# top.net
KiCad netlist of a schematic drawn in Altium Designer
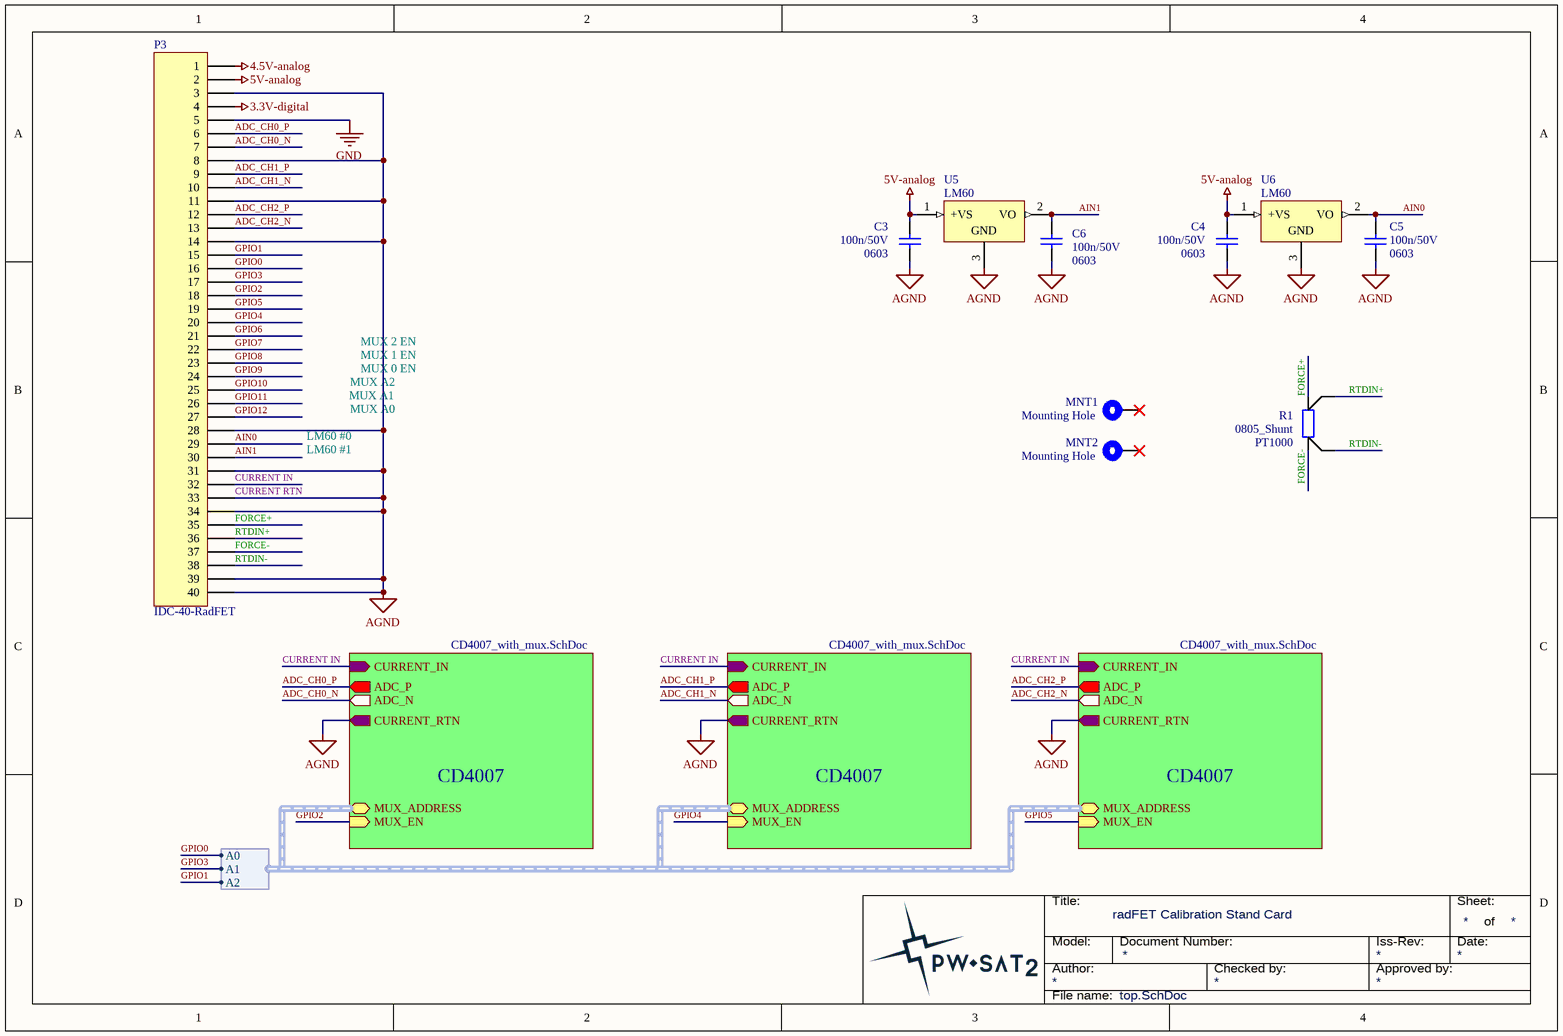
[diagram p0: top.SchDoc]

(export (version "E")
  (design (tool "Eeschema 10.0.6"))
  (components
    (comp (ref "C3")
      (value "100n/50V")
      (footprint "SMD_Capacitor_0603")
      (description "Ceramic Cap Kemet COTS 100n/50V X7R 0603")
      (fields
        (field (name "MANUFACTURER") "Kemet")
        (field (name "MANUFACTURERPARTNUMBER") "C0603T104K5RALTU")
        (field (name "PACKAGE") "0603")
      )
      (libsource (lib "capacitors") (part "Cer_C0603T104K5RALTU"))
    )
    (comp (ref "C4")
      (value "100n/50V")
      (footprint "SMD_Capacitor_0603")
      (description "Ceramic Cap Kemet COTS 100n/50V X7R 0603")
      (fields
        (field (name "MANUFACTURER") "Kemet")
        (field (name "MANUFACTURERPARTNUMBER") "C0603T104K5RALTU")
        (field (name "PACKAGE") "0603")
      )
      (libsource (lib "capacitors") (part "Cer_C0603T104K5RALTU"))
    )
    (comp (ref "C5")
      (value "100n/50V")
      (footprint "SMD_Capacitor_0603")
      (description "Ceramic Cap Kemet COTS 100n/50V X7R 0603")
      (fields
        (field (name "MANUFACTURER") "Kemet")
        (field (name "MANUFACTURERPARTNUMBER") "C0603T104K5RALTU")
        (field (name "PACKAGE") "0603")
      )
      (libsource (lib "capacitors") (part "Cer_C0603T104K5RALTU"))
    )
    (comp (ref "C6")
      (value "100n/50V")
      (footprint "SMD_Capacitor_0603")
      (description "Ceramic Cap Kemet COTS 100n/50V X7R 0603")
      (fields
        (field (name "MANUFACTURER") "Kemet")
        (field (name "MANUFACTURERPARTNUMBER") "C0603T104K5RALTU")
        (field (name "PACKAGE") "0603")
      )
      (libsource (lib "capacitors") (part "Cer_C0603T104K5RALTU"))
    )
    (comp (ref "MNT1")
      (value "Mounting Hole")
      (footprint "PC-104_PcbMntHole_M3")
      (description "PCB Mounting Hole")
      (libsource (lib "connectors_printed-circuit-board") (part "MntHole"))
    )
    (comp (ref "MNT2")
      (value "Mounting Hole")
      (footprint "PC-104_PcbMntHole_M3")
      (description "PCB Mounting Hole")
      (libsource (lib "connectors_printed-circuit-board") (part "MntHole"))
    )
    (comp (ref "P3")
      (value "IDC-40-RadFET")
      (footprint "IDC-40-Male-Socket-Angle")
      (fields (field (name "PUBLISHER") "Altium Limited"))
      (libsource (lib "GG") (part "IDC-40-RadFET"))
    )
    (comp (ref "R1")
      (value "PT1000")
      (footprint "SMD_Resistor-shunt_0805")
      (description "Platinum Thin-Film Chip Sensor")
      (fields
        (field (name "MANUFACTURER") "IST INNOVATIVE SENSOR TECHNOLOGY")
        (field (name "MANUFACTURERPARTNUMBER") "P1K0.0805.2P.A")
        (field (name "PACKAGE") "0805_Shunt")
      )
      (libsource (lib "resistors") (part "PT1000"))
    )
    (comp (ref "U5")
      (value "LM60")
      (footprint "SOT23-3")
      (description "Analog temperature sensor")
      (libsource (lib "microcircuits") (part "LM60"))
    )
    (comp (ref "U6")
      (value "LM60")
      (footprint "SOT23-3")
      (description "Analog temperature sensor")
      (libsource (lib "microcircuits") (part "LM60"))
    )
  )
  (nets
    (net (code "2") (name "/ADC_CH0_N") (class "Default")
      (node (ref "P3") (pin "7") (pinfunction "7_7") (pintype "passive"))
    )
    (net (code "3") (name "/ADC_CH0_P") (class "Default")
      (node (ref "P3") (pin "6") (pinfunction "6_6") (pintype "passive"))
    )
    (net (code "4") (name "/ADC_CH1_N") (class "Default")
      (node (ref "P3") (pin "10") (pinfunction "10_10") (pintype "passive"))
    )
    (net (code "5") (name "/ADC_CH1_P") (class "Default")
      (node (ref "P3") (pin "9") (pinfunction "9_9") (pintype "passive"))
    )
    (net (code "6") (name "/ADC_CH2_N") (class "Default")
      (node (ref "P3") (pin "13") (pinfunction "13_13") (pintype "passive"))
    )
    (net (code "7") (name "/ADC_CH2_P") (class "Default")
      (node (ref "P3") (pin "12") (pinfunction "12_12") (pintype "passive"))
    )
    (net (code "8") (name "/AIN0") (class "Default")
      (node (ref "C5") (pin "1") (pinfunction "1_1") (pintype "passive"))
      (node (ref "P3") (pin "29") (pinfunction "29_29") (pintype "passive"))
      (node (ref "U6") (pin "2") (pinfunction "VO_2") (pintype "output"))
    )
    (net (code "9") (name "/AIN1") (class "Default")
      (node (ref "C6") (pin "1") (pinfunction "1_1") (pintype "passive"))
      (node (ref "P3") (pin "30") (pinfunction "30_30") (pintype "passive"))
      (node (ref "U5") (pin "2") (pinfunction "VO_2") (pintype "output"))
    )
    (net (code "10") (name "/CURRENT IN") (class "Default")
      (node (ref "P3") (pin "32") (pinfunction "32_32") (pintype "passive"))
    )
    (net (code "11") (name "/FORCE+") (class "Default")
      (node (ref "P3") (pin "35") (pinfunction "35_35") (pintype "passive"))
      (node (ref "R1") (pin "4") (pinfunction "4_4") (pintype "passive"))
    )
    (net (code "12") (name "/FORCE-") (class "Default")
      (node (ref "P3") (pin "37") (pinfunction "37_37") (pintype "passive"))
      (node (ref "R1") (pin "1") (pinfunction "1_1") (pintype "passive"))
    )
    (net (code "13") (name "/GPIO0") (class "Default")
      (node (ref "P3") (pin "16") (pinfunction "16_16") (pintype "passive"))
    )
    (net (code "14") (name "/GPIO1") (class "Default")
      (node (ref "P3") (pin "15") (pinfunction "15_15") (pintype "passive"))
    )
    (net (code "15") (name "/GPIO2") (class "Default")
      (node (ref "P3") (pin "18") (pinfunction "18_18") (pintype "passive"))
    )
    (net (code "16") (name "/GPIO3") (class "Default")
      (node (ref "P3") (pin "17") (pinfunction "17_17") (pintype "passive"))
    )
    (net (code "17") (name "/GPIO4") (class "Default")
      (node (ref "P3") (pin "20") (pinfunction "20_20") (pintype "passive"))
    )
    (net (code "18") (name "/GPIO5") (class "Default")
      (node (ref "P3") (pin "19") (pinfunction "19_19") (pintype "passive"))
    )
    (net (code "19") (name "/GPIO6") (class "Default")
      (node (ref "P3") (pin "21") (pinfunction "21_21") (pintype "passive"))
    )
    (net (code "20") (name "/GPIO7") (class "Default")
      (node (ref "P3") (pin "22") (pinfunction "22_22") (pintype "passive"))
    )
    (net (code "21") (name "/GPIO8") (class "Default")
      (node (ref "P3") (pin "23") (pinfunction "23_23") (pintype "passive"))
    )
    (net (code "22") (name "/GPIO9") (class "Default")
      (node (ref "P3") (pin "24") (pinfunction "24_24") (pintype "passive"))
    )
    (net (code "23") (name "/GPIO10") (class "Default")
      (node (ref "P3") (pin "25") (pinfunction "25_25") (pintype "passive"))
    )
    (net (code "24") (name "/GPIO11") (class "Default")
      (node (ref "P3") (pin "26") (pinfunction "26_26") (pintype "passive"))
    )
    (net (code "25") (name "/GPIO12") (class "Default")
      (node (ref "P3") (pin "27") (pinfunction "27_27") (pintype "passive"))
    )
    (net (code "26") (name "/RTDIN+") (class "Default")
      (node (ref "P3") (pin "36") (pinfunction "36_36") (pintype "passive"))
      (node (ref "R1") (pin "3") (pinfunction "3_3") (pintype "passive"))
    )
    (net (code "27") (name "/RTDIN-") (class "Default")
      (node (ref "P3") (pin "38") (pinfunction "38_38") (pintype "passive"))
      (node (ref "R1") (pin "2") (pinfunction "2_2") (pintype "passive"))
    )
    (net (code "29") (name "3.3V-digital") (class "Default")
      (node (ref "P3") (pin "4") (pinfunction "4_4") (pintype "passive"))
    )
    (net (code "30") (name "4.5V-analog") (class "Default")
      (node (ref "P3") (pin "1") (pinfunction "1_1") (pintype "passive"))
    )
    (net (code "31") (name "5V-analog") (class "Default")
      (node (ref "C3") (pin "1") (pinfunction "1_1") (pintype "passive"))
      (node (ref "C4") (pin "1") (pinfunction "1_1") (pintype "passive"))
      (node (ref "P3") (pin "2") (pinfunction "2_2") (pintype "passive"))
      (node (ref "U5") (pin "1") (pinfunction "+VS_1") (pintype "input"))
      (node (ref "U6") (pin "1") (pinfunction "+VS_1") (pintype "input"))
    )
    (net (code "32") (name "AGND") (class "Default")
      (node (ref "C3") (pin "2") (pinfunction "2_2") (pintype "passive"))
      (node (ref "C4") (pin "2") (pinfunction "2_2") (pintype "passive"))
      (node (ref "C5") (pin "2") (pinfunction "2_2") (pintype "passive"))
      (node (ref "C6") (pin "2") (pinfunction "2_2") (pintype "passive"))
      (node (ref "P3") (pin "11") (pinfunction "11_11") (pintype "passive"))
      (node (ref "P3") (pin "14") (pinfunction "14_14") (pintype "passive"))
      (node (ref "P3") (pin "28") (pinfunction "28_28") (pintype "passive"))
      (node (ref "P3") (pin "3") (pinfunction "3_3") (pintype "passive"))
      (node (ref "P3") (pin "31") (pinfunction "31_31") (pintype "passive"))
      (node (ref "P3") (pin "33") (pinfunction "33_33") (pintype "passive"))
      (node (ref "P3") (pin "34") (pinfunction "34_34") (pintype "passive"))
      (node (ref "P3") (pin "39") (pinfunction "39_39") (pintype "passive"))
      (node (ref "P3") (pin "40") (pinfunction "40_40") (pintype "passive"))
      (node (ref "P3") (pin "8") (pinfunction "8_8") (pintype "passive"))
      (node (ref "U5") (pin "3") (pinfunction "GND_3") (pintype "power_in"))
      (node (ref "U6") (pin "3") (pinfunction "GND_3") (pintype "power_in"))
    )
    (net (code "33") (name "GND") (class "Default")
      (node (ref "P3") (pin "5") (pinfunction "5_5") (pintype "passive"))
    )
    (net (code "34") (name "unconnected-(MNT1-Pad1)") (class "Default")
      (node (ref "MNT1") (pin "1") (pinfunction "1_1") (pintype "passive+no_connect"))
    )
    (net (code "35") (name "unconnected-(MNT2-Pad1)") (class "Default")
      (node (ref "MNT2") (pin "1") (pinfunction "1_1") (pintype "passive+no_connect"))
    )
  )
)
